# TPSM84824MOL.net
KiCad netlist of a schematic drawn in Altium Designer
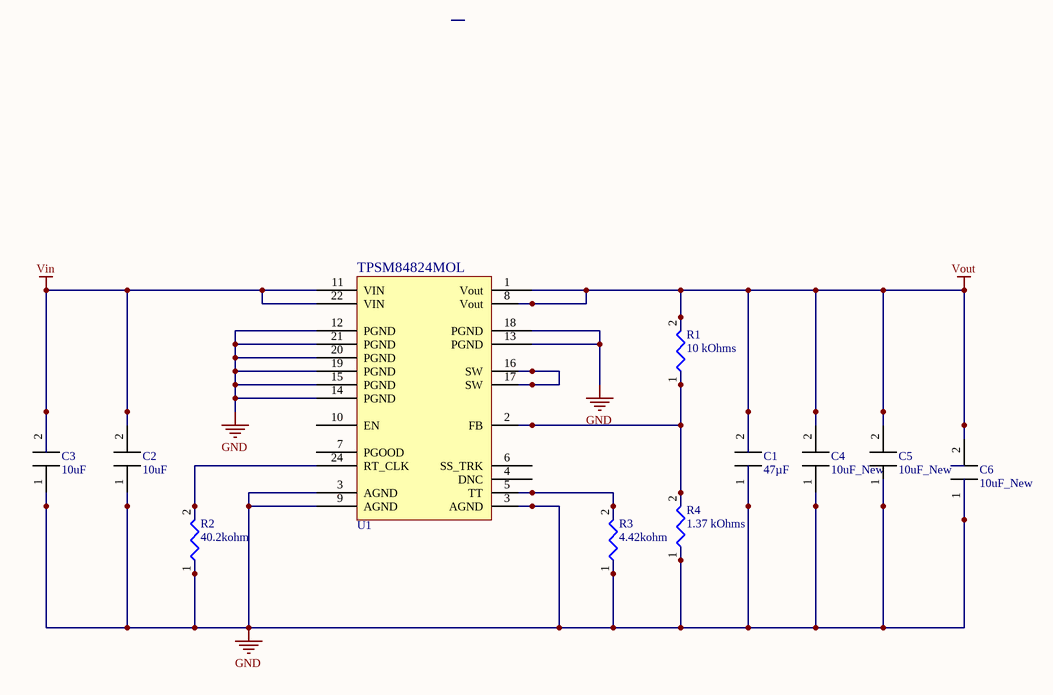
[diagram p0: TPSM84824MOL.SchDoc]

(export (version "E")
  (design (tool "Eeschema 10.0.6"))
  (components
    (comp (ref "C1")
      (value "47µF")
      (footprint "C/R0805")
      (description "47µF 6.3V Ceramic Capacitor X5R 0805 (2012 Metric) 0.079\" L x 0.049\" W (2.00mm x 1.25mm)")
      (fields
        (field (name "MANUFACTURER") "Murata")
        (field (name "MANUFACTURER PART NUMBER") "GRM21BR60J476ME15K")
      )
      (libsource (lib "TPSM84824MOL_PCB_Library") (part "GRM21BR60J476ME15K"))
    )
    (comp (ref "C2")
      (value "10uF")
      (footprint "C/R0805")
      (description "CAP CER 10UF 10V X5R 0805")
      (fields
        (field (name "MANUFACTURER") "KEMET")
        (field (name "MANUFACTURER PART NUMBER") "C0805C106K8PACTU")
      )
      (libsource (lib "TPSM84824MOL_PCB_Library") (part "C0805C106K8PACTU"))
    )
    (comp (ref "C3")
      (value "10uF")
      (footprint "C/R0805")
      (description "CAP CER 10UF 10V X5R 0805")
      (fields
        (field (name "MANUFACTURER") "KEMET")
        (field (name "MANUFACTURER PART NUMBER") "C0805C106K8PACTU")
      )
      (libsource (lib "TPSM84824MOL_PCB_Library") (part "C0805C106K8PACTU"))
    )
    (comp (ref "C4")
      (value "10uF_New")
      (footprint "CAPPM7343X310N")
      (description "CAP TANT 10UF 35V 20% 2917")
      (fields
        (field (name "MANUFACTURER") "KEMET")
        (field (name "MANUFACTURER PART NUMBER") "T495D106M035ATE125")
      )
      (libsource (lib "TPS54622_Schematic_Library") (part "T495D106M035ATE125"))
    )
    (comp (ref "C5")
      (value "10uF_New")
      (footprint "CAPPM7343X310N")
      (description "CAP TANT 10UF 35V 20% 2917")
      (fields
        (field (name "MANUFACTURER") "KEMET")
        (field (name "MANUFACTURER PART NUMBER") "T495D106M035ATE125")
      )
      (libsource (lib "TPS54622_Schematic_Library") (part "T495D106M035ATE125"))
    )
    (comp (ref "C6")
      (value "10uF_New")
      (footprint "CAPPM7343X310N")
      (description "CAP TANT 10UF 35V 20% 2917")
      (fields
        (field (name "MANUFACTURER") "KEMET")
        (field (name "MANUFACTURER PART NUMBER") "T495D106M035ATE125")
      )
      (libsource (lib "TPS54622_Schematic_Library") (part "T495D106M035ATE125"))
    )
    (comp (ref "R1")
      (value "10 kOhms")
      (footprint "C/R0805")
      (description "RES SMD 10K OHM 1% 1/8W 0805")
      (fields
        (field (name "MANUFACTURER") "Yageo")
        (field (name "MANUFACTURER PART NUMBER") "RC0805FR-0710KL")
      )
      (libsource (lib "TPSM84824MOL_PCB_Library") (part "RC0805FR-0710KL"))
    )
    (comp (ref "R2")
      (value "40.2kohm")
      (footprint "C/R0805")
      (description "Res Thin Film 0805 40.2K Ohm 0.1% 1/8W 25ppm/C Molded SMD SMD Punched Carrier T/R")
      (fields
        (field (name "MANUFACTURER") "Panasonic")
        (field (name "MANUFACTURER PART NUMBER") "ERA-6AEB4022V")
      )
      (libsource (lib "TPSM84824MOL_PCB_Library") (part "ERA-6AEB4022V"))
    )
    (comp (ref "R3")
      (value "4.42kohm")
      (footprint "C/R0805")
      (description "Panasonic ERA Series Thin Film Surface Mount Fixed Resistor 0805 Case 4.42k 0.1% 0.125W 25ppm/C")
      (fields
        (field (name "MANUFACTURER") "Panasonic")
        (field (name "MANUFACTURER PART NUMBER") "ERA-6AEB4421V")
      )
      (libsource (lib "TPSM84824MOL_PCB_Library") (part "ERA-6AEB4421V"))
    )
    (comp (ref "R4")
      (value "1.37 kOhms")
      (footprint "C/R0805")
      (description "RES SMD 1.37K OHM 1% 1/16W 0402")
      (fields
        (field (name "MANUFACTURER") "Vishay")
        (field (name "MANUFACTURER PART NUMBER") "CRCW04021K37FKED")
      )
      (libsource (lib "TPSM84824MOL_PCB_Library") (part "RC0805FR-071K37L"))
    )
    (comp (ref "U1")
      (value "TPSM84824MOL")
      (footprint "TPSM84424MOLR")
      (description "DC DC CONVERTER 0.6-10V")
      (fields
        (field (name "MANUFACTURER") "Texas Instruments")
        (field (name "MANUFACTURER PART NUMBER") "TPSM84824MOLR")
      )
      (libsource (lib "TPSM84824MOL_PCB_Library") (part "TPSM84824MOL"))
    )
  )
  (nets
    (net (code "1") (name "GND") (class "Default")
      (node (ref "C1") (pin "1") (pinfunction "1_1") (pintype "passive"))
      (node (ref "C2") (pin "1") (pinfunction "1_1") (pintype "passive"))
      (node (ref "C3") (pin "1") (pinfunction "1_1") (pintype "passive"))
      (node (ref "C4") (pin "1") (pinfunction "1_1") (pintype "passive"))
      (node (ref "C5") (pin "1") (pinfunction "1_1") (pintype "passive"))
      (node (ref "C6") (pin "1") (pinfunction "1_1") (pintype "passive"))
      (node (ref "R2") (pin "1") (pinfunction "1_1") (pintype "passive"))
      (node (ref "R3") (pin "1") (pinfunction "1_1") (pintype "passive"))
      (node (ref "R4") (pin "1") (pinfunction "1_1") (pintype "passive"))
      (node (ref "U1") (pin "12") (pinfunction "PGND_12") (pintype "passive"))
      (node (ref "U1") (pin "13") (pinfunction "PGND_13") (pintype "passive"))
      (node (ref "U1") (pin "14") (pinfunction "PGND_14") (pintype "passive"))
      (node (ref "U1") (pin "15") (pinfunction "PGND_15") (pintype "passive"))
      (node (ref "U1") (pin "18") (pinfunction "PGND_18") (pintype "passive"))
      (node (ref "U1") (pin "19") (pinfunction "PGND_19") (pintype "passive"))
      (node (ref "U1") (pin "20") (pinfunction "PGND_20") (pintype "passive"))
      (node (ref "U1") (pin "21") (pinfunction "PGND_21") (pintype "passive"))
      (node (ref "U1") (pin "3") (pinfunction "AGND_3") (pintype "passive"))
      (node (ref "U1") (pin "9") (pinfunction "AGND_9") (pintype "passive"))
    )
    (net (code "2") (name "Net-(R3-6)") (class "Default")
      (node (ref "R3") (pin "2") (pinfunction "6_2") (pintype "passive"))
      (node (ref "U1") (pin "5") (pinfunction "TT_5") (pintype "passive"))
    )
    (net (code "3") (name "Net-(U1-FB)") (class "Default")
      (node (ref "R1") (pin "1") (pinfunction "1_1") (pintype "passive"))
      (node (ref "R4") (pin "2") (pinfunction "2_2") (pintype "passive"))
      (node (ref "U1") (pin "2") (pinfunction "FB_2") (pintype "passive"))
    )
    (net (code "4") (name "Net-(U1-RT_CLK)") (class "Default")
      (node (ref "R2") (pin "2") (pinfunction "2_2") (pintype "passive"))
      (node (ref "U1") (pin "24") (pinfunction "RT_CLK_24") (pintype "passive"))
    )
    (net (code "5") (name "Net-(U1-SW-Pad16)") (class "Default")
      (node (ref "U1") (pin "16") (pinfunction "SW_16") (pintype "passive"))
      (node (ref "U1") (pin "17") (pinfunction "SW_17") (pintype "passive"))
    )
    (net (code "6") (name "Vin") (class "Default")
      (node (ref "C2") (pin "2") (pinfunction "2_2") (pintype "passive"))
      (node (ref "C3") (pin "2") (pinfunction "2_2") (pintype "passive"))
      (node (ref "U1") (pin "11") (pinfunction "VIN_11") (pintype "passive"))
      (node (ref "U1") (pin "22") (pinfunction "VIN_22") (pintype "passive"))
    )
    (net (code "7") (name "Vout") (class "Default")
      (node (ref "C1") (pin "2") (pinfunction "2_2") (pintype "passive"))
      (node (ref "C4") (pin "2") (pinfunction "2_2") (pintype "passive"))
      (node (ref "C5") (pin "2") (pinfunction "2_2") (pintype "passive"))
      (node (ref "C6") (pin "2") (pinfunction "2_2") (pintype "passive"))
      (node (ref "R1") (pin "2") (pinfunction "2_2") (pintype "passive"))
      (node (ref "U1") (pin "1") (pinfunction "Vout_1") (pintype "passive"))
      (node (ref "U1") (pin "8") (pinfunction "Vout_8") (pintype "passive"))
    )
    (net (code "8") (name "unconnected-(U1-DNC-Pad4)") (class "Default")
      (node (ref "U1") (pin "4") (pinfunction "DNC_4") (pintype "passive"))
    )
    (net (code "9") (name "unconnected-(U1-EN-Pad10)") (class "Default")
      (node (ref "U1") (pin "10") (pinfunction "EN_10") (pintype "passive"))
    )
    (net (code "10") (name "unconnected-(U1-PGOOD-Pad7)") (class "Default")
      (node (ref "U1") (pin "7") (pinfunction "PGOOD_7") (pintype "passive"))
    )
    (net (code "11") (name "unconnected-(U1-SS_TRK-Pad6)") (class "Default")
      (node (ref "U1") (pin "6") (pinfunction "SS_TRK_6") (pintype "passive"))
    )
  )
)
